# Canzasi-Wrtr.net
KiCad netlist of a schematic drawn in EAGLE
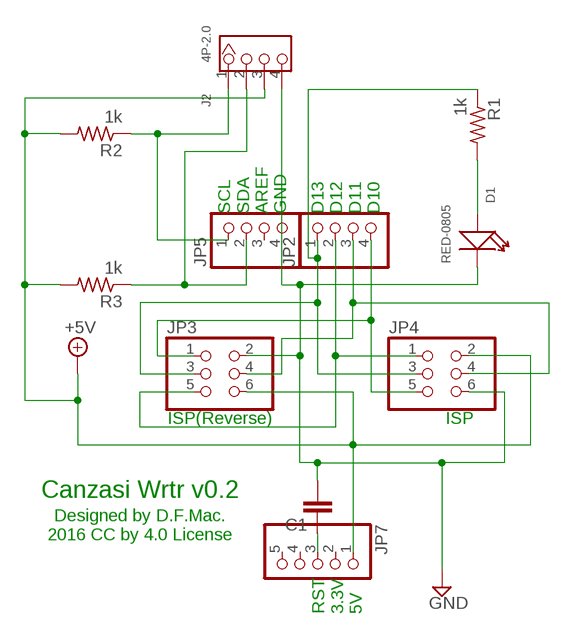
[diagram p0: schematic, sheet 1]

(export (version "E")
  (design (tool "Eeschema 10.0.6"))
  (components
    (comp (ref "C1")
      (value "C-EUC0805")
      (footprint "eagle-import:C0805")
      (libsource (lib "eagle-import") (part "C-EUC0805"))
    )
    (comp (ref "D1")
      (value "RED-0805")
      (footprint "eagle-import:LED-0805")
      (fields (field (name "MPN") "17-215SURC/S530-A2/TR8"))
      (libsource (lib "eagle-import") (part "SMD-LED-CLEAR-RED(0805)"))
    )
    (comp (ref "J2")
      (value "4P-2.0")
      (footprint "eagle-import:HW4-2.0")
      (libsource (lib "eagle-import") (part "GROVE-CONNECTOR-DIP(4P-2.0)"))
    )
    (comp (ref "JP2")
      (value "PINHD-1X4")
      (footprint "eagle-import:1X04")
      (libsource (lib "eagle-import") (part "PINHD-1X4"))
    )
    (comp (ref "JP3")
      (value "PINHD-2X3")
      (footprint "eagle-import:2X03")
      (libsource (lib "eagle-import") (part "PINHD-2X3"))
    )
    (comp (ref "JP4")
      (value "PINHD-2X3")
      (footprint "eagle-import:2X03")
      (libsource (lib "eagle-import") (part "PINHD-2X3"))
    )
    (comp (ref "JP5")
      (value "PINHD-1X4")
      (footprint "eagle-import:1X04")
      (libsource (lib "eagle-import") (part "PINHD-1X4"))
    )
    (comp (ref "JP7")
      (value "PINHD-1X5")
      (footprint "eagle-import:1X05")
      (libsource (lib "eagle-import") (part "PINHD-1X5"))
    )
    (comp (ref "R1")
      (value "1k")
      (footprint "eagle-import:R0603")
      (libsource (lib "eagle-import") (part "R-US_R0603"))
    )
    (comp (ref "R2")
      (value "1k")
      (footprint "eagle-import:R0603")
      (libsource (lib "eagle-import") (part "R-US_R0603"))
    )
    (comp (ref "R3")
      (value "1k")
      (footprint "eagle-import:R0603")
      (libsource (lib "eagle-import") (part "R-US_R0603"))
    )
  )
  (nets
    (net (code "1") (name "+5V") (class "Default")
      (node (ref "J2") (pin "3") (pinfunction "3_3") (pintype "bidirectional"))
      (node (ref "JP3") (pin "6") (pinfunction "6_6") (pintype "passive"))
      (node (ref "JP4") (pin "2") (pinfunction "2_2") (pintype "passive"))
      (node (ref "JP7") (pin "1") (pinfunction "1_1") (pintype "passive"))
      (node (ref "R2") (pin "2") (pinfunction "2_2") (pintype "passive"))
      (node (ref "R3") (pin "2") (pinfunction "2_2") (pintype "passive"))
    )
    (net (code "2") (name "GND") (class "Default")
      (node (ref "C1") (pin "2") (pinfunction "2_2") (pintype "passive"))
      (node (ref "D1") (pin "-") (pinfunction "-_-") (pintype "passive"))
      (node (ref "J2") (pin "4") (pinfunction "4_4") (pintype "bidirectional"))
      (node (ref "JP3") (pin "2") (pinfunction "2_2") (pintype "passive"))
      (node (ref "JP4") (pin "6") (pinfunction "6_6") (pintype "passive"))
      (node (ref "JP5") (pin "4") (pinfunction "4_4") (pintype "passive"))
    )
    (net (code "3") (name "Net-(C1-Pad1)") (class "Default")
      (node (ref "C1") (pin "1") (pinfunction "1_1") (pintype "passive"))
      (node (ref "JP7") (pin "3") (pinfunction "3_3") (pintype "passive"))
    )
    (net (code "4") (name "Net-(D1-Pad+)") (class "Default")
      (node (ref "D1") (pin "+") (pinfunction "+_+") (pintype "passive"))
      (node (ref "R1") (pin "2") (pinfunction "2_2") (pintype "passive"))
    )
    (net (code "5") (name "Net-(J2-Pad1)") (class "Default")
      (node (ref "J2") (pin "1") (pinfunction "1_1") (pintype "bidirectional"))
      (node (ref "JP5") (pin "1") (pinfunction "1_1") (pintype "passive"))
      (node (ref "R2") (pin "1") (pinfunction "1_1") (pintype "passive"))
    )
    (net (code "6") (name "Net-(J2-Pad2)") (class "Default")
      (node (ref "J2") (pin "2") (pinfunction "2_2") (pintype "bidirectional"))
      (node (ref "JP5") (pin "2") (pinfunction "2_2") (pintype "passive"))
      (node (ref "R3") (pin "1") (pinfunction "1_1") (pintype "passive"))
    )
    (net (code "7") (name "Net-(JP2-Pad1)") (class "Default")
      (node (ref "JP2") (pin "1") (pinfunction "1_1") (pintype "passive"))
      (node (ref "JP3") (pin "3") (pinfunction "3_3") (pintype "passive"))
      (node (ref "JP4") (pin "3") (pinfunction "3_3") (pintype "passive"))
      (node (ref "R1") (pin "1") (pinfunction "1_1") (pintype "passive"))
    )
    (net (code "8") (name "Net-(JP2-Pad2)") (class "Default")
      (node (ref "JP2") (pin "2") (pinfunction "2_2") (pintype "passive"))
      (node (ref "JP3") (pin "5") (pinfunction "5_5") (pintype "passive"))
      (node (ref "JP4") (pin "1") (pinfunction "1_1") (pintype "passive"))
    )
    (net (code "9") (name "Net-(JP2-Pad3)") (class "Default")
      (node (ref "JP2") (pin "3") (pinfunction "3_3") (pintype "passive"))
      (node (ref "JP3") (pin "4") (pinfunction "4_4") (pintype "passive"))
      (node (ref "JP4") (pin "4") (pinfunction "4_4") (pintype "passive"))
    )
    (net (code "10") (name "Net-(JP2-Pad4)") (class "Default")
      (node (ref "JP2") (pin "4") (pinfunction "4_4") (pintype "passive"))
      (node (ref "JP3") (pin "1") (pinfunction "1_1") (pintype "passive"))
      (node (ref "JP4") (pin "5") (pinfunction "5_5") (pintype "passive"))
    )
    (net (code "11") (name "unconnected-(JP5-Pad3)") (class "Default")
      (node (ref "JP5") (pin "3") (pinfunction "3_3") (pintype "passive"))
    )
    (net (code "12") (name "unconnected-(JP7-Pad2)") (class "Default")
      (node (ref "JP7") (pin "2") (pinfunction "2_2") (pintype "passive"))
    )
    (net (code "13") (name "unconnected-(JP7-Pad4)") (class "Default")
      (node (ref "JP7") (pin "4") (pinfunction "4_4") (pintype "passive"))
    )
    (net (code "14") (name "unconnected-(JP7-Pad5)") (class "Default")
      (node (ref "JP7") (pin "5") (pinfunction "5_5") (pintype "passive"))
    )
  )
)
